# display.net
KiCad netlist of a schematic drawn in EAGLE
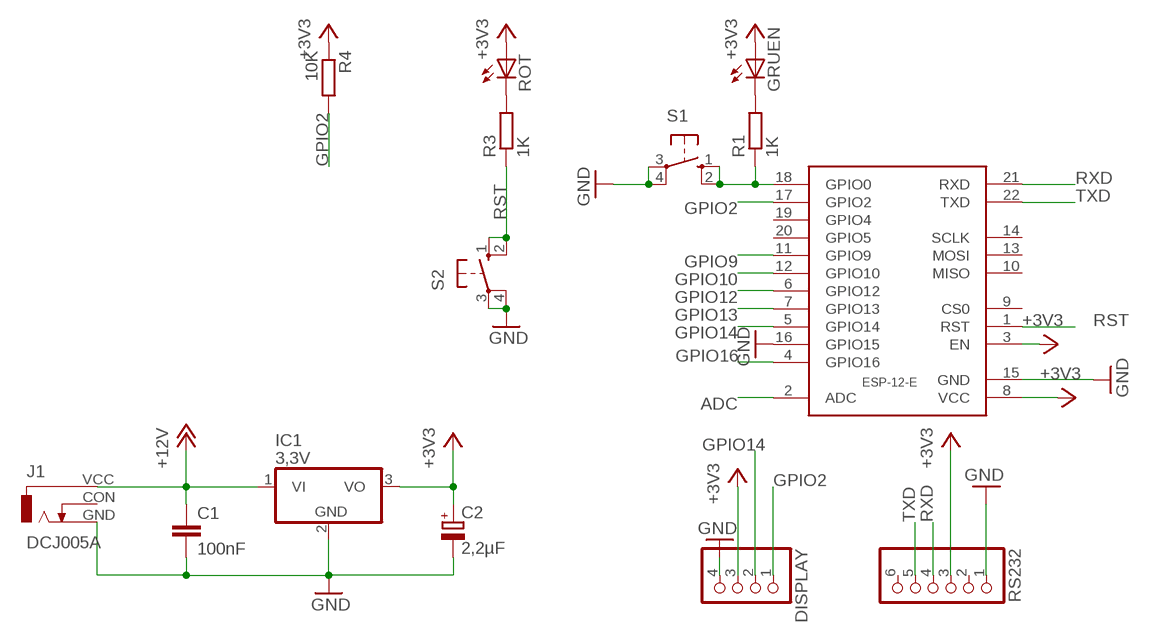
[diagram p0: schematic, sheet 1]

(export (version "E")
  (design (tool "Eeschema 10.0.6"))
  (components
    (comp (ref "C1")
      (value "100nF")
      (footprint "eagle-import:C050-030X075")
      (libsource (lib "eagle-import") (part "C-EU050-030X075"))
    )
    (comp (ref "C2")
      (value "2,2µF")
      (footprint "eagle-import:E2,5-6")
      (libsource (lib "eagle-import") (part "CPOL-EUE2.5-6"))
    )
    (comp (ref "DISPLAY")
      (value "PINHD-1X4")
      (footprint "eagle-import:1X04")
      (libsource (lib "eagle-import") (part "PINHD-1X4"))
    )
    (comp (ref "GRUEN")
      (value "LED5MM")
      (footprint "eagle-import:LED5MM")
      (libsource (lib "eagle-import") (part "LED5MM"))
    )
    (comp (ref "IC1")
      (value "3,3V")
      (footprint "eagle-import:TO220V")
      (libsource (lib "eagle-import") (part "78TV05"))
    )
    (comp (ref "J1")
      (value "DCJ005A")
      (footprint "eagle-import:DC005A")
      (libsource (lib "eagle-import") (part "DCJ005A"))
    )
    (comp (ref "R1")
      (value "1K")
      (footprint "eagle-import:0207_10")
      (libsource (lib "eagle-import") (part "R-EU_0207/10"))
    )
    (comp (ref "R3")
      (value "1K")
      (footprint "eagle-import:0207_10")
      (libsource (lib "eagle-import") (part "R-EU_0207/10"))
    )
    (comp (ref "R4")
      (value "10K")
      (footprint "eagle-import:0207_10")
      (libsource (lib "eagle-import") (part "R-EU_0207/10"))
    )
    (comp (ref "ROT")
      (value "LED5MM")
      (footprint "eagle-import:LED5MM")
      (libsource (lib "eagle-import") (part "LED5MM"))
    )
    (comp (ref "RS232")
      (value "PINHD-1X6")
      (footprint "eagle-import:1X06")
      (libsource (lib "eagle-import") (part "PINHD-1X6"))
    )
    (comp (ref "S1")
      (value "10-XX")
      (footprint "eagle-import:B3F-10XX")
      (fields (field (name "MPN") "B3F-1000"))
      (libsource (lib "eagle-import") (part "10-XX"))
    )
    (comp (ref "S2")
      (value "10-XX")
      (footprint "eagle-import:B3F-10XX")
      (fields (field (name "MPN") "B3F-1000"))
      (libsource (lib "eagle-import") (part "10-XX"))
    )
    (comp (ref "U$1")
      (value "ESP-12-E")
      (footprint "eagle-import:ESP-12-E")
      (libsource (lib "eagle-import") (part "ESP-12-E"))
    )
  )
  (nets
    (net (code "1") (name "+3V3") (class "Default")
      (node (ref "C2") (pin "+") (pinfunction "+_+") (pintype "passive"))
      (node (ref "DISPLAY") (pin "3") (pinfunction "3_3") (pintype "passive"))
      (node (ref "GRUEN") (pin "A") (pinfunction "A_A") (pintype "passive"))
      (node (ref "IC1") (pin "3") (pinfunction "VO_3") (pintype "passive"))
      (node (ref "R4") (pin "1") (pinfunction "1_1") (pintype "passive"))
      (node (ref "ROT") (pin "A") (pinfunction "A_A") (pintype "passive"))
      (node (ref "RS232") (pin "3") (pinfunction "3_3") (pintype "passive"))
      (node (ref "U$1") (pin "3") (pinfunction "EN_3") (pintype "bidirectional"))
      (node (ref "U$1") (pin "8") (pinfunction "VCC_8") (pintype "power_in"))
    )
    (net (code "2") (name "+12V") (class "Default")
      (node (ref "C1") (pin "1") (pinfunction "1_1") (pintype "passive"))
      (node (ref "IC1") (pin "1") (pinfunction "VI_1") (pintype "input"))
      (node (ref "J1") (pin "VCC") (pinfunction "1_VCC") (pintype "passive"))
    )
    (net (code "3") (name "/ADC") (class "Default")
      (node (ref "U$1") (pin "2") (pinfunction "ADC_2") (pintype "bidirectional"))
    )
    (net (code "4") (name "/GPIO2") (class "Default")
      (node (ref "DISPLAY") (pin "1") (pinfunction "1_1") (pintype "passive"))
      (node (ref "R4") (pin "2") (pinfunction "2_2") (pintype "passive"))
      (node (ref "U$1") (pin "17") (pinfunction "GPIO2_17") (pintype "bidirectional"))
    )
    (net (code "5") (name "/GPIO9") (class "Default")
      (node (ref "U$1") (pin "11") (pinfunction "GPIO9_11") (pintype "bidirectional"))
    )
    (net (code "6") (name "/GPIO10") (class "Default")
      (node (ref "U$1") (pin "12") (pinfunction "GPIO10_12") (pintype "bidirectional"))
    )
    (net (code "7") (name "/GPIO12") (class "Default")
      (node (ref "U$1") (pin "6") (pinfunction "GPIO12_6") (pintype "bidirectional"))
    )
    (net (code "8") (name "/GPIO13") (class "Default")
      (node (ref "U$1") (pin "7") (pinfunction "GPIO13_7") (pintype "bidirectional"))
    )
    (net (code "9") (name "/GPIO14") (class "Default")
      (node (ref "DISPLAY") (pin "2") (pinfunction "2_2") (pintype "passive"))
      (node (ref "U$1") (pin "5") (pinfunction "GPIO14_5") (pintype "bidirectional"))
    )
    (net (code "10") (name "/GPIO16") (class "Default")
      (node (ref "U$1") (pin "4") (pinfunction "GPIO16_4") (pintype "bidirectional"))
    )
    (net (code "11") (name "/RST") (class "Default")
      (node (ref "R3") (pin "1") (pinfunction "1_1") (pintype "passive"))
      (node (ref "S2") (pin "1") (pinfunction "S_1") (pintype "passive"))
      (node (ref "S2") (pin "2") (pinfunction "S1_2") (pintype "passive"))
      (node (ref "U$1") (pin "1") (pinfunction "RST_1") (pintype "bidirectional"))
    )
    (net (code "12") (name "/RXD") (class "Default")
      (node (ref "RS232") (pin "4") (pinfunction "4_4") (pintype "passive"))
      (node (ref "U$1") (pin "21") (pinfunction "RXD_21") (pintype "bidirectional"))
    )
    (net (code "13") (name "/TXD") (class "Default")
      (node (ref "RS232") (pin "5") (pinfunction "5_5") (pintype "passive"))
      (node (ref "U$1") (pin "22") (pinfunction "TXD_22") (pintype "bidirectional"))
    )
    (net (code "14") (name "GND") (class "Default")
      (node (ref "C1") (pin "2") (pinfunction "2_2") (pintype "passive"))
      (node (ref "C2") (pin "-") (pinfunction "-_-") (pintype "passive"))
      (node (ref "DISPLAY") (pin "4") (pinfunction "4_4") (pintype "passive"))
      (node (ref "IC1") (pin "2") (pinfunction "GND_2") (pintype "passive"))
      (node (ref "J1") (pin "GND") (pinfunction "3_GND") (pintype "passive"))
      (node (ref "RS232") (pin "1") (pinfunction "1_1") (pintype "passive"))
      (node (ref "S1") (pin "3") (pinfunction "P_3") (pintype "passive"))
      (node (ref "S1") (pin "4") (pinfunction "P1_4") (pintype "passive"))
      (node (ref "S2") (pin "3") (pinfunction "P_3") (pintype "passive"))
      (node (ref "S2") (pin "4") (pinfunction "P1_4") (pintype "passive"))
      (node (ref "U$1") (pin "15") (pinfunction "GND_15") (pintype "power_in"))
      (node (ref "U$1") (pin "16") (pinfunction "GPIO15_16") (pintype "bidirectional"))
    )
    (net (code "15") (name "Net-(GRUEN-C)") (class "Default")
      (node (ref "GRUEN") (pin "K") (pinfunction "C_K") (pintype "passive"))
      (node (ref "R1") (pin "2") (pinfunction "2_2") (pintype "passive"))
    )
    (net (code "16") (name "Net-(ROT-C)") (class "Default")
      (node (ref "R3") (pin "2") (pinfunction "2_2") (pintype "passive"))
      (node (ref "ROT") (pin "K") (pinfunction "C_K") (pintype "passive"))
    )
    (net (code "17") (name "Net-(S1-S)") (class "Default")
      (node (ref "R1") (pin "1") (pinfunction "1_1") (pintype "passive"))
      (node (ref "S1") (pin "1") (pinfunction "S_1") (pintype "passive"))
      (node (ref "S1") (pin "2") (pinfunction "S1_2") (pintype "passive"))
      (node (ref "U$1") (pin "18") (pinfunction "GPIO0_18") (pintype "bidirectional"))
    )
    (net (code "18") (name "unconnected-(J1-2-PadCON)") (class "Default")
      (node (ref "J1") (pin "CON") (pinfunction "2_CON") (pintype "passive"))
    )
    (net (code "19") (name "unconnected-(RS232-Pad2)") (class "Default")
      (node (ref "RS232") (pin "2") (pinfunction "2_2") (pintype "passive"))
    )
    (net (code "20") (name "unconnected-(RS232-Pad6)") (class "Default")
      (node (ref "RS232") (pin "6") (pinfunction "6_6") (pintype "passive"))
    )
    (net (code "21") (name "unconnected-(U$1-CS0-Pad9)") (class "Default")
      (node (ref "U$1") (pin "9") (pinfunction "CS0_9") (pintype "bidirectional"))
    )
    (net (code "22") (name "unconnected-(U$1-GPIO4-Pad19)") (class "Default")
      (node (ref "U$1") (pin "19") (pinfunction "GPIO4_19") (pintype "bidirectional"))
    )
    (net (code "23") (name "unconnected-(U$1-GPIO5-Pad20)") (class "Default")
      (node (ref "U$1") (pin "20") (pinfunction "GPIO5_20") (pintype "bidirectional"))
    )
    (net (code "24") (name "unconnected-(U$1-MISO-Pad10)") (class "Default")
      (node (ref "U$1") (pin "10") (pinfunction "MISO_10") (pintype "bidirectional"))
    )
    (net (code "25") (name "unconnected-(U$1-MOSI-Pad13)") (class "Default")
      (node (ref "U$1") (pin "13") (pinfunction "MOSI_13") (pintype "bidirectional"))
    )
    (net (code "26") (name "unconnected-(U$1-SCLK-Pad14)") (class "Default")
      (node (ref "U$1") (pin "14") (pinfunction "SCLK_14") (pintype "bidirectional"))
    )
  )
)
